# power_supply.net
KiCad netlist of a schematic drawn in EAGLE
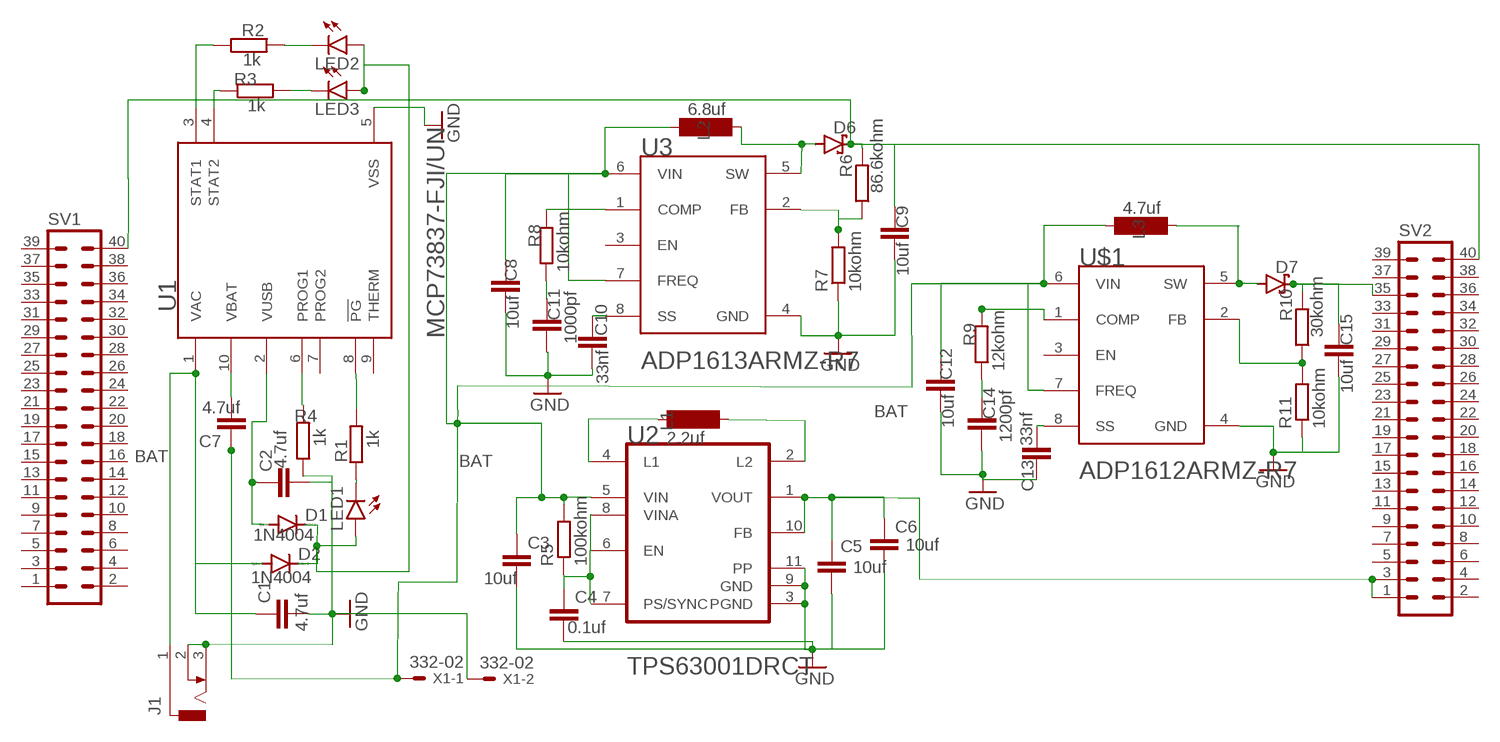
[diagram p0: schematic, sheet 1]

(export (version "E")
  (design (tool "Eeschema 10.0.6"))
  (components
    (comp (ref "C1")
      (value "4.7uf")
      (footprint "eagle-import:C025-024X044")
      (libsource (lib "eagle-import") (part "C-EU025-024X044"))
    )
    (comp (ref "C2")
      (value "4.7uf")
      (footprint "eagle-import:C025-024X044")
      (libsource (lib "eagle-import") (part "C-EU025-024X044"))
    )
    (comp (ref "C3")
      (value "10uf")
      (footprint "eagle-import:C0201")
      (libsource (lib "eagle-import") (part "C-EUC0201"))
    )
    (comp (ref "C4")
      (value "0.1uf")
      (footprint "eagle-import:C0201")
      (libsource (lib "eagle-import") (part "C-EUC0201"))
    )
    (comp (ref "C5")
      (value "10uf")
      (footprint "eagle-import:C0201")
      (libsource (lib "eagle-import") (part "C-EUC0201"))
    )
    (comp (ref "C6")
      (value "10uf")
      (footprint "eagle-import:C0201")
      (libsource (lib "eagle-import") (part "C-EUC0201"))
    )
    (comp (ref "C7")
      (value "4.7uf")
      (footprint "eagle-import:C025-024X044")
      (libsource (lib "eagle-import") (part "C-EU025-024X044"))
    )
    (comp (ref "C8")
      (value "10uf")
      (footprint "eagle-import:C0201")
      (libsource (lib "eagle-import") (part "C-EUC0201"))
    )
    (comp (ref "C9")
      (value "10uf")
      (footprint "eagle-import:C0201")
      (libsource (lib "eagle-import") (part "C-EUC0201"))
    )
    (comp (ref "C10")
      (value "33nf")
      (footprint "eagle-import:C0201")
      (libsource (lib "eagle-import") (part "C-EUC0201"))
    )
    (comp (ref "C11")
      (value "1000pf")
      (footprint "eagle-import:C0201")
      (libsource (lib "eagle-import") (part "C-EUC0201"))
    )
    (comp (ref "C12")
      (value "10uf")
      (footprint "eagle-import:C0201")
      (libsource (lib "eagle-import") (part "C-EUC0201"))
    )
    (comp (ref "C13")
      (value "33nf")
      (footprint "eagle-import:C0201")
      (libsource (lib "eagle-import") (part "C-EUC0201"))
    )
    (comp (ref "C14")
      (value "1200pf")
      (footprint "eagle-import:C0201")
      (libsource (lib "eagle-import") (part "C-EUC0201"))
    )
    (comp (ref "C15")
      (value "10uf")
      (footprint "eagle-import:C0201")
      (libsource (lib "eagle-import") (part "C-EUC0201"))
    )
    (comp (ref "D1")
      (value "1N4004")
      (footprint "eagle-import:DO41-10")
      (libsource (lib "eagle-import") (part "1N4004"))
    )
    (comp (ref "D2")
      (value "1N4004")
      (footprint "eagle-import:DO41-10")
      (libsource (lib "eagle-import") (part "1N4004"))
    )
    (comp (ref "D6")
      (value "P4KEXX")
      (footprint "eagle-import:DO41-10")
      (libsource (lib "eagle-import") (part "P4KEXX"))
    )
    (comp (ref "D7")
      (value "P4KEXX")
      (footprint "eagle-import:DO41-10")
      (libsource (lib "eagle-import") (part "P4KEXX"))
    )
    (comp (ref "J1")
      (value "DCJ0303")
      (footprint "eagle-import:DCJ0303")
      (libsource (lib "eagle-import") (part "DCJ0303"))
    )
    (comp (ref "L1")
      (value "2.2uf")
      (footprint "eagle-import:SD75")
      (libsource (lib "eagle-import") (part "SD75"))
    )
    (comp (ref "L2")
      (value "6.8uf")
      (footprint "eagle-import:SD75")
      (libsource (lib "eagle-import") (part "SD75"))
    )
    (comp (ref "L3")
      (value "4.7uf")
      (footprint "eagle-import:SD75")
      (libsource (lib "eagle-import") (part "SD75"))
    )
    (comp (ref "LED1")
      (value "LED")
      (footprint "eagle-import:SMARTLED-TTW")
      (libsource (lib "eagle-import") (part "LED"))
    )
    (comp (ref "LED2")
      (value "LED")
      (footprint "eagle-import:SMARTLED-TTW")
      (libsource (lib "eagle-import") (part "LED"))
    )
    (comp (ref "LED3")
      (value "LED")
      (footprint "eagle-import:SMARTLED-TTW")
      (libsource (lib "eagle-import") (part "LED"))
    )
    (comp (ref "R1")
      (value "1k")
      (footprint "eagle-import:R01005")
      (libsource (lib "eagle-import") (part "R-EU_01005"))
    )
    (comp (ref "R2")
      (value "1k")
      (footprint "eagle-import:R01005")
      (libsource (lib "eagle-import") (part "R-EU_01005"))
    )
    (comp (ref "R3")
      (value "1k")
      (footprint "eagle-import:R01005")
      (libsource (lib "eagle-import") (part "R-EU_01005"))
    )
    (comp (ref "R4")
      (value "1k")
      (footprint "eagle-import:R01005")
      (libsource (lib "eagle-import") (part "R-EU_01005"))
    )
    (comp (ref "R5")
      (value "100kohm")
      (footprint "eagle-import:R01005")
      (libsource (lib "eagle-import") (part "R-EU_01005"))
    )
    (comp (ref "R6")
      (value "86.6kohm")
      (footprint "eagle-import:R01005")
      (libsource (lib "eagle-import") (part "R-EU_01005"))
    )
    (comp (ref "R7")
      (value "10kohm")
      (footprint "eagle-import:R01005")
      (libsource (lib "eagle-import") (part "R-EU_01005"))
    )
    (comp (ref "R8")
      (value "10kohm")
      (footprint "eagle-import:R01005")
      (libsource (lib "eagle-import") (part "R-EU_01005"))
    )
    (comp (ref "R9")
      (value "12kohm")
      (footprint "eagle-import:R01005")
      (libsource (lib "eagle-import") (part "R-EU_01005"))
    )
    (comp (ref "R10")
      (value "30kohm")
      (footprint "eagle-import:R01005")
      (libsource (lib "eagle-import") (part "R-EU_01005"))
    )
    (comp (ref "R11")
      (value "10kohm")
      (footprint "eagle-import:R01005")
      (libsource (lib "eagle-import") (part "R-EU_01005"))
    )
    (comp (ref "SV1")
      (value "40P")
      (footprint "eagle-import:40P")
      (libsource (lib "eagle-import") (part "40P"))
    )
    (comp (ref "SV2")
      (value "40P")
      (footprint "eagle-import:40P")
      (libsource (lib "eagle-import") (part "40P"))
    )
    (comp (ref "U$1")
      (value "ADP1612")
      (footprint "eagle-import:ADP1612")
      (libsource (lib "eagle-import") (part "ADP1612"))
    )
    (comp (ref "U1")
      (value "MICROCHIP_MCP73837-FJI-UNMICROCHIP_MCP73837-FJI-UN_0_0")
      (footprint "eagle-import:MICROCHIP_MCP73837-FJI-UN_0")
      (fields
        (field (name "DIGIKEY_PART_NUMBER") "MCP73837-FJI/UN-ND")
        (field (name "MF") "Microchip")
        (field (name "MOUSER_PART_NUMBER") "579-MCP73837-FJI/UN")
      )
      (libsource (lib "eagle-import") (part "MICROCHIP_MCP73837-FJI-UNMICROCHIP_MCP73837-FJI-UN_0_0"))
    )
    (comp (ref "U2")
      (value "TEXAS_INSTRUMENTS_TPS63001DRCTTEXAS_INSTRUMENTS_TPS63001DRCT_0_0")
      (footprint "eagle-import:TEXAS_INSTRUMENTS_TPS63001DRCT_0")
      (fields (field (name "MF") "Texas Instruments") (field (name "MPN") "TPS63001DRCT"))
      (libsource (lib "eagle-import") (part "TEXAS_INSTRUMENTS_TPS63001DRCTTEXAS_INSTRUMENTS_TPS63001DRCT_0_0"))
    )
    (comp (ref "U3")
      (value "ANALOG_DEVICES_INC_ADP1613ARMZ-R7ANALOG_DEVICES_INC_ADP1613ARMZ-R7_0_0")
      (footprint "eagle-import:ANALOG_DEVICES_INC_ADP1613ARMZ-R7_0")
      (fields
        (field (name "DIGIKEY_PART_NUMBER") "ADP1613ARMZ-R7CT-ND")
        (field (name "MF") "Analog Devices Inc")
        (field (name "MOUSER_PART_NUMBER") "584-ADP1613ARMZ-R7")
      )
      (libsource (lib "eagle-import") (part "ANALOG_DEVICES_INC_ADP1613ARMZ-R7ANALOG_DEVICES_INC_ADP1613ARMZ-R7_0_0"))
    )
    (comp (ref "X1")
      (value "332-02")
      (footprint "eagle-import:332-02")
      (libsource (lib "eagle-import") (part "332-02"))
    )
  )
  (nets
    (net (code "1") (name "/BAT") (class "Default")
      (node (ref "C12") (pin "1") (pinfunction "1_1") (pintype "passive"))
      (node (ref "C3") (pin "1") (pinfunction "1_1") (pintype "passive"))
      (node (ref "C7") (pin "1") (pinfunction "1_1") (pintype "passive"))
      (node (ref "C8") (pin "1") (pinfunction "1_1") (pintype "passive"))
      (node (ref "L2") (pin "1") (pinfunction "1_1") (pintype "passive"))
      (node (ref "L3") (pin "1") (pinfunction "1_1") (pintype "passive"))
      (node (ref "R5") (pin "2") (pinfunction "2_2") (pintype "passive"))
      (node (ref "U$1") (pin "6") (pinfunction "VIN_6") (pintype "bidirectional"))
      (node (ref "U$1") (pin "7") (pinfunction "FREQ_7") (pintype "bidirectional"))
      (node (ref "U2") (pin "5") (pinfunction "VIN_5") (pintype "power_in"))
      (node (ref "U3") (pin "6") (pinfunction "VIN_6") (pintype "bidirectional"))
      (node (ref "U3") (pin "7") (pinfunction "FREQ_7") (pintype "bidirectional"))
      (node (ref "X1") (pin "1") (pinfunction "S_1") (pintype "passive"))
    )
    (net (code "2") (name "GND") (class "Default")
      (node (ref "C1") (pin "2") (pinfunction "2_2") (pintype "passive"))
      (node (ref "C10") (pin "2") (pinfunction "2_2") (pintype "passive"))
      (node (ref "C11") (pin "2") (pinfunction "2_2") (pintype "passive"))
      (node (ref "C12") (pin "2") (pinfunction "2_2") (pintype "passive"))
      (node (ref "C13") (pin "1") (pinfunction "1_1") (pintype "passive"))
      (node (ref "C14") (pin "2") (pinfunction "2_2") (pintype "passive"))
      (node (ref "C15") (pin "2") (pinfunction "2_2") (pintype "passive"))
      (node (ref "C2") (pin "2") (pinfunction "2_2") (pintype "passive"))
      (node (ref "C3") (pin "2") (pinfunction "2_2") (pintype "passive"))
      (node (ref "C4") (pin "2") (pinfunction "2_2") (pintype "passive"))
      (node (ref "C5") (pin "2") (pinfunction "2_2") (pintype "passive"))
      (node (ref "C6") (pin "2") (pinfunction "2_2") (pintype "passive"))
      (node (ref "C8") (pin "2") (pinfunction "2_2") (pintype "passive"))
      (node (ref "C9") (pin "2") (pinfunction "2_2") (pintype "passive"))
      (node (ref "J1") (pin "2") (pinfunction "2_2") (pintype "passive"))
      (node (ref "J1") (pin "3") (pinfunction "3_3") (pintype "passive"))
      (node (ref "R11") (pin "1") (pinfunction "1_1") (pintype "passive"))
      (node (ref "R4") (pin "1") (pinfunction "1_1") (pintype "passive"))
      (node (ref "R7") (pin "1") (pinfunction "1_1") (pintype "passive"))
      (node (ref "U$1") (pin "4") (pinfunction "GND_4") (pintype "power_in"))
      (node (ref "U1") (pin "5") (pinfunction "VSS_5") (pintype "bidirectional"))
      (node (ref "U2") (pin "11") (pinfunction "PP_11") (pintype "power_in"))
      (node (ref "U2") (pin "3") (pinfunction "PGND_3") (pintype "power_in"))
      (node (ref "U2") (pin "9") (pinfunction "GND_9") (pintype "power_in"))
      (node (ref "U3") (pin "4") (pinfunction "GND_4") (pintype "power_in"))
      (node (ref "X1") (pin "2") (pinfunction "S_2") (pintype "passive"))
    )
    (net (code "3") (name "Net-(C9-Pad1)") (class "Default")
      (node (ref "C9") (pin "1") (pinfunction "1_1") (pintype "passive"))
      (node (ref "D6") (pin "C") (pinfunction "C_C") (pintype "passive"))
      (node (ref "R6") (pin "2") (pinfunction "2_2") (pintype "passive"))
      (node (ref "SV1") (pin "40") (pinfunction "40_40") (pintype "passive"))
      (node (ref "SV2") (pin "40") (pinfunction "40_40") (pintype "passive"))
    )
    (net (code "4") (name "Net-(C11-Pad1)") (class "Default")
      (node (ref "C11") (pin "1") (pinfunction "1_1") (pintype "passive"))
      (node (ref "R8") (pin "1") (pinfunction "1_1") (pintype "passive"))
    )
    (net (code "5") (name "Net-(C14-Pad1)") (class "Default")
      (node (ref "C14") (pin "1") (pinfunction "1_1") (pintype "passive"))
      (node (ref "R9") (pin "1") (pinfunction "1_1") (pintype "passive"))
    )
    (net (code "6") (name "Net-(C15-Pad1)") (class "Default")
      (node (ref "C15") (pin "1") (pinfunction "1_1") (pintype "passive"))
      (node (ref "D7") (pin "C") (pinfunction "C_C") (pintype "passive"))
      (node (ref "R10") (pin "2") (pinfunction "2_2") (pintype "passive"))
      (node (ref "SV2") (pin "35") (pinfunction "35_35") (pintype "passive"))
    )
    (net (code "7") (name "Net-(LED1-A)") (class "Default")
      (node (ref "D1") (pin "C") (pinfunction "C_C") (pintype "passive"))
      (node (ref "D2") (pin "C") (pinfunction "C_C") (pintype "passive"))
      (node (ref "LED1") (pin "A@1") (pinfunction "A_A@1") (pintype "passive"))
      (node (ref "LED2") (pin "A@1") (pinfunction "A_A@1") (pintype "passive"))
      (node (ref "LED3") (pin "A@1") (pinfunction "A_A@1") (pintype "passive"))
    )
    (net (code "8") (name "Net-(LED1-C)") (class "Default")
      (node (ref "LED1") (pin "C@1") (pinfunction "C_C@1") (pintype "passive"))
      (node (ref "R1") (pin "1") (pinfunction "1_1") (pintype "passive"))
    )
    (net (code "9") (name "Net-(LED2-C)") (class "Default")
      (node (ref "LED2") (pin "C@1") (pinfunction "C_C@1") (pintype "passive"))
      (node (ref "R2") (pin "2") (pinfunction "2_2") (pintype "passive"))
    )
    (net (code "10") (name "Net-(LED3-C)") (class "Default")
      (node (ref "LED3") (pin "C@1") (pinfunction "C_C@1") (pintype "passive"))
      (node (ref "R3") (pin "2") (pinfunction "2_2") (pintype "passive"))
    )
    (net (code "11") (name "Net-(U$1-COMP)") (class "Default")
      (node (ref "R9") (pin "2") (pinfunction "2_2") (pintype "passive"))
      (node (ref "U$1") (pin "1") (pinfunction "COMP_1") (pintype "bidirectional"))
    )
    (net (code "12") (name "Net-(U$1-FB)") (class "Default")
      (node (ref "R10") (pin "1") (pinfunction "1_1") (pintype "passive"))
      (node (ref "R11") (pin "2") (pinfunction "2_2") (pintype "passive"))
      (node (ref "U$1") (pin "2") (pinfunction "FB_2") (pintype "bidirectional"))
    )
    (net (code "13") (name "Net-(U$1-SS)") (class "Default")
      (node (ref "C13") (pin "2") (pinfunction "2_2") (pintype "passive"))
      (node (ref "U$1") (pin "8") (pinfunction "SS_8") (pintype "bidirectional"))
    )
    (net (code "14") (name "Net-(U$1-SW)") (class "Default")
      (node (ref "D7") (pin "A") (pinfunction "A_A") (pintype "passive"))
      (node (ref "U$1") (pin "5") (pinfunction "SW_5") (pintype "bidirectional"))
    )
    (net (code "15") (name "Net-(U1-PROG1)") (class "Default")
      (node (ref "R4") (pin "2") (pinfunction "2_2") (pintype "passive"))
      (node (ref "U1") (pin "6") (pinfunction "PROG1_6") (pintype "bidirectional"))
    )
    (net (code "16") (name "Net-(U1-STAT1)") (class "Default")
      (node (ref "R2") (pin "1") (pinfunction "1_1") (pintype "passive"))
      (node (ref "U1") (pin "3") (pinfunction "STAT1_3") (pintype "bidirectional"))
    )
    (net (code "17") (name "Net-(U1-STAT2)") (class "Default")
      (node (ref "R3") (pin "1") (pinfunction "1_1") (pintype "passive"))
      (node (ref "U1") (pin "4") (pinfunction "STAT2_4") (pintype "bidirectional"))
    )
    (net (code "18") (name "Net-(U1-VAC)") (class "Default")
      (node (ref "C1") (pin "1") (pinfunction "1_1") (pintype "passive"))
      (node (ref "D2") (pin "A") (pinfunction "A_A") (pintype "passive"))
      (node (ref "J1") (pin "1") (pinfunction "1_1") (pintype "passive"))
      (node (ref "U1") (pin "1") (pinfunction "VAC_1") (pintype "bidirectional"))
    )
    (net (code "19") (name "Net-(U1-VBAT)") (class "Default")
      (node (ref "C7") (pin "2") (pinfunction "2_2") (pintype "passive"))
      (node (ref "U1") (pin "10") (pinfunction "VBAT_10") (pintype "bidirectional"))
    )
    (net (code "20") (name "Net-(U1-VUSB)") (class "Default")
      (node (ref "C2") (pin "1") (pinfunction "1_1") (pintype "passive"))
      (node (ref "D1") (pin "A") (pinfunction "A_A") (pintype "passive"))
      (node (ref "U1") (pin "2") (pinfunction "VUSB_2") (pintype "bidirectional"))
    )
    (net (code "21") (name "Net-(U1-~{PG})") (class "Default")
      (node (ref "R1") (pin "2") (pinfunction "2_2") (pintype "passive"))
      (node (ref "U1") (pin "8") (pinfunction "~{PG}_8") (pintype "bidirectional"))
    )
    (net (code "22") (name "Net-(U2-EN)") (class "Default")
      (node (ref "C4") (pin "1") (pinfunction "1_1") (pintype "passive"))
      (node (ref "R5") (pin "1") (pinfunction "1_1") (pintype "passive"))
      (node (ref "U2") (pin "6") (pinfunction "EN_6") (pintype "input"))
      (node (ref "U2") (pin "7") (pinfunction "PS/SYNC_7") (pintype "input"))
      (node (ref "U2") (pin "8") (pinfunction "VINA_8") (pintype "power_in"))
    )
    (net (code "23") (name "Net-(U2-FB)") (class "Default")
      (node (ref "C5") (pin "1") (pinfunction "1_1") (pintype "passive"))
      (node (ref "C6") (pin "1") (pinfunction "1_1") (pintype "passive"))
      (node (ref "SV2") (pin "1") (pinfunction "1_1") (pintype "passive"))
      (node (ref "SV2") (pin "3") (pinfunction "3_3") (pintype "passive"))
      (node (ref "U2") (pin "1") (pinfunction "VOUT_1") (pintype "power_in"))
      (node (ref "U2") (pin "10") (pinfunction "FB_10") (pintype "input"))
    )
    (net (code "24") (name "Net-(U2-L1)") (class "Default")
      (node (ref "L1") (pin "1") (pinfunction "1_1") (pintype "passive"))
      (node (ref "U2") (pin "4") (pinfunction "L1_4") (pintype "passive"))
    )
    (net (code "25") (name "Net-(U2-L2)") (class "Default")
      (node (ref "L1") (pin "2") (pinfunction "2_2") (pintype "passive"))
      (node (ref "U2") (pin "2") (pinfunction "L2_2") (pintype "passive"))
    )
    (net (code "26") (name "Net-(U3-COMP)") (class "Default")
      (node (ref "R8") (pin "2") (pinfunction "2_2") (pintype "passive"))
      (node (ref "U3") (pin "1") (pinfunction "COMP_1") (pintype "bidirectional"))
    )
    (net (code "27") (name "Net-(U3-FB)") (class "Default")
      (node (ref "R6") (pin "1") (pinfunction "1_1") (pintype "passive"))
      (node (ref "R7") (pin "2") (pinfunction "2_2") (pintype "passive"))
      (node (ref "U3") (pin "2") (pinfunction "FB_2") (pintype "bidirectional"))
    )
    (net (code "28") (name "Net-(U3-SS)") (class "Default")
      (node (ref "C10") (pin "1") (pinfunction "1_1") (pintype "passive"))
      (node (ref "U3") (pin "8") (pinfunction "SS_8") (pintype "bidirectional"))
    )
    (net (code "29") (name "Net-(U3-SW)") (class "Default")
      (node (ref "D6") (pin "A") (pinfunction "A_A") (pintype "passive"))
      (node (ref "L2") (pin "2") (pinfunction "2_2") (pintype "passive"))
      (node (ref "U3") (pin "5") (pinfunction "SW_5") (pintype "bidirectional"))
    )
    (net (code "30") (name "unconnected-(L3-Pad2)") (class "Default")
      (node (ref "L3") (pin "2") (pinfunction "2_2") (pintype "passive"))
    )
    (net (code "31") (name "unconnected-(SV1-Pad1)") (class "Default")
      (node (ref "SV1") (pin "1") (pinfunction "1_1") (pintype "passive"))
    )
    (net (code "32") (name "unconnected-(SV1-Pad2)") (class "Default")
      (node (ref "SV1") (pin "2") (pinfunction "2_2") (pintype "passive"))
    )
    (net (code "33") (name "unconnected-(SV1-Pad3)") (class "Default")
      (node (ref "SV1") (pin "3") (pinfunction "3_3") (pintype "passive"))
    )
    (net (code "34") (name "unconnected-(SV1-Pad4)") (class "Default")
      (node (ref "SV1") (pin "4") (pinfunction "4_4") (pintype "passive"))
    )
    (net (code "35") (name "unconnected-(SV1-Pad5)") (class "Default")
      (node (ref "SV1") (pin "5") (pinfunction "5_5") (pintype "passive"))
    )
    (net (code "36") (name "unconnected-(SV1-Pad6)") (class "Default")
      (node (ref "SV1") (pin "6") (pinfunction "6_6") (pintype "passive"))
    )
    (net (code "37") (name "unconnected-(SV1-Pad7)") (class "Default")
      (node (ref "SV1") (pin "7") (pinfunction "7_7") (pintype "passive"))
    )
    (net (code "38") (name "unconnected-(SV1-Pad8)") (class "Default")
      (node (ref "SV1") (pin "8") (pinfunction "8_8") (pintype "passive"))
    )
    (net (code "39") (name "unconnected-(SV1-Pad9)") (class "Default")
      (node (ref "SV1") (pin "9") (pinfunction "9_9") (pintype "passive"))
    )
    (net (code "40") (name "unconnected-(SV1-Pad10)") (class "Default")
      (node (ref "SV1") (pin "10") (pinfunction "10_10") (pintype "passive"))
    )
    (net (code "41") (name "unconnected-(SV1-Pad11)") (class "Default")
      (node (ref "SV1") (pin "11") (pinfunction "11_11") (pintype "passive"))
    )
    (net (code "42") (name "unconnected-(SV1-Pad12)") (class "Default")
      (node (ref "SV1") (pin "12") (pinfunction "12_12") (pintype "passive"))
    )
    (net (code "43") (name "unconnected-(SV1-Pad13)") (class "Default")
      (node (ref "SV1") (pin "13") (pinfunction "13_13") (pintype "passive"))
    )
    (net (code "44") (name "unconnected-(SV1-Pad14)") (class "Default")
      (node (ref "SV1") (pin "14") (pinfunction "14_14") (pintype "passive"))
    )
    (net (code "45") (name "unconnected-(SV1-Pad15)") (class "Default")
      (node (ref "SV1") (pin "15") (pinfunction "15_15") (pintype "passive"))
    )
    (net (code "46") (name "unconnected-(SV1-Pad16)") (class "Default")
      (node (ref "SV1") (pin "16") (pinfunction "16_16") (pintype "passive"))
    )
    (net (code "47") (name "unconnected-(SV1-Pad17)") (class "Default")
      (node (ref "SV1") (pin "17") (pinfunction "17_17") (pintype "passive"))
    )
    (net (code "48") (name "unconnected-(SV1-Pad18)") (class "Default")
      (node (ref "SV1") (pin "18") (pinfunction "18_18") (pintype "passive"))
    )
    (net (code "49") (name "unconnected-(SV1-Pad19)") (class "Default")
      (node (ref "SV1") (pin "19") (pinfunction "19_19") (pintype "passive"))
    )
    (net (code "50") (name "unconnected-(SV1-Pad20)") (class "Default")
      (node (ref "SV1") (pin "20") (pinfunction "20_20") (pintype "passive"))
    )
    (net (code "51") (name "unconnected-(SV1-Pad21)") (class "Default")
      (node (ref "SV1") (pin "21") (pinfunction "21_21") (pintype "passive"))
    )
    (net (code "52") (name "unconnected-(SV1-Pad22)") (class "Default")
      (node (ref "SV1") (pin "22") (pinfunction "22_22") (pintype "passive"))
    )
    (net (code "53") (name "unconnected-(SV1-Pad23)") (class "Default")
      (node (ref "SV1") (pin "23") (pinfunction "23_23") (pintype "passive"))
    )
    (net (code "54") (name "unconnected-(SV1-Pad24)") (class "Default")
      (node (ref "SV1") (pin "24") (pinfunction "24_24") (pintype "passive"))
    )
    (net (code "55") (name "unconnected-(SV1-Pad25)") (class "Default")
      (node (ref "SV1") (pin "25") (pinfunction "25_25") (pintype "passive"))
    )
    (net (code "56") (name "unconnected-(SV1-Pad26)") (class "Default")
      (node (ref "SV1") (pin "26") (pinfunction "26_26") (pintype "passive"))
    )
    (net (code "57") (name "unconnected-(SV1-Pad27)") (class "Default")
      (node (ref "SV1") (pin "27") (pinfunction "27_27") (pintype "passive"))
    )
    (net (code "58") (name "unconnected-(SV1-Pad28)") (class "Default")
      (node (ref "SV1") (pin "28") (pinfunction "28_28") (pintype "passive"))
    )
    (net (code "59") (name "unconnected-(SV1-Pad29)") (class "Default")
      (node (ref "SV1") (pin "29") (pinfunction "29_29") (pintype "passive"))
    )
    (net (code "60") (name "unconnected-(SV1-Pad30)") (class "Default")
      (node (ref "SV1") (pin "30") (pinfunction "30_30") (pintype "passive"))
    )
    (net (code "61") (name "unconnected-(SV1-Pad31)") (class "Default")
      (node (ref "SV1") (pin "31") (pinfunction "31_31") (pintype "passive"))
    )
    (net (code "62") (name "unconnected-(SV1-Pad32)") (class "Default")
      (node (ref "SV1") (pin "32") (pinfunction "32_32") (pintype "passive"))
    )
    (net (code "63") (name "unconnected-(SV1-Pad33)") (class "Default")
      (node (ref "SV1") (pin "33") (pinfunction "33_33") (pintype "passive"))
    )
    (net (code "64") (name "unconnected-(SV1-Pad34)") (class "Default")
      (node (ref "SV1") (pin "34") (pinfunction "34_34") (pintype "passive"))
    )
    (net (code "65") (name "unconnected-(SV1-Pad35)") (class "Default")
      (node (ref "SV1") (pin "35") (pinfunction "35_35") (pintype "passive"))
    )
    (net (code "66") (name "unconnected-(SV1-Pad36)") (class "Default")
      (node (ref "SV1") (pin "36") (pinfunction "36_36") (pintype "passive"))
    )
    (net (code "67") (name "unconnected-(SV1-Pad37)") (class "Default")
      (node (ref "SV1") (pin "37") (pinfunction "37_37") (pintype "passive"))
    )
    (net (code "68") (name "unconnected-(SV1-Pad38)") (class "Default")
      (node (ref "SV1") (pin "38") (pinfunction "38_38") (pintype "passive"))
    )
    (net (code "69") (name "unconnected-(SV1-Pad39)") (class "Default")
      (node (ref "SV1") (pin "39") (pinfunction "39_39") (pintype "passive"))
    )
    (net (code "70") (name "unconnected-(SV2-Pad2)") (class "Default")
      (node (ref "SV2") (pin "2") (pinfunction "2_2") (pintype "passive"))
    )
    (net (code "71") (name "unconnected-(SV2-Pad4)") (class "Default")
      (node (ref "SV2") (pin "4") (pinfunction "4_4") (pintype "passive"))
    )
    (net (code "72") (name "unconnected-(SV2-Pad5)") (class "Default")
      (node (ref "SV2") (pin "5") (pinfunction "5_5") (pintype "passive"))
    )
    (net (code "73") (name "unconnected-(SV2-Pad6)") (class "Default")
      (node (ref "SV2") (pin "6") (pinfunction "6_6") (pintype "passive"))
    )
    (net (code "74") (name "unconnected-(SV2-Pad7)") (class "Default")
      (node (ref "SV2") (pin "7") (pinfunction "7_7") (pintype "passive"))
    )
    (net (code "75") (name "unconnected-(SV2-Pad8)") (class "Default")
      (node (ref "SV2") (pin "8") (pinfunction "8_8") (pintype "passive"))
    )
    (net (code "76") (name "unconnected-(SV2-Pad9)") (class "Default")
      (node (ref "SV2") (pin "9") (pinfunction "9_9") (pintype "passive"))
    )
    (net (code "77") (name "unconnected-(SV2-Pad10)") (class "Default")
      (node (ref "SV2") (pin "10") (pinfunction "10_10") (pintype "passive"))
    )
    (net (code "78") (name "unconnected-(SV2-Pad11)") (class "Default")
      (node (ref "SV2") (pin "11") (pinfunction "11_11") (pintype "passive"))
    )
    (net (code "79") (name "unconnected-(SV2-Pad12)") (class "Default")
      (node (ref "SV2") (pin "12") (pinfunction "12_12") (pintype "passive"))
    )
    (net (code "80") (name "unconnected-(SV2-Pad13)") (class "Default")
      (node (ref "SV2") (pin "13") (pinfunction "13_13") (pintype "passive"))
    )
    (net (code "81") (name "unconnected-(SV2-Pad14)") (class "Default")
      (node (ref "SV2") (pin "14") (pinfunction "14_14") (pintype "passive"))
    )
    (net (code "82") (name "unconnected-(SV2-Pad15)") (class "Default")
      (node (ref "SV2") (pin "15") (pinfunction "15_15") (pintype "passive"))
    )
    (net (code "83") (name "unconnected-(SV2-Pad16)") (class "Default")
      (node (ref "SV2") (pin "16") (pinfunction "16_16") (pintype "passive"))
    )
    (net (code "84") (name "unconnected-(SV2-Pad17)") (class "Default")
      (node (ref "SV2") (pin "17") (pinfunction "17_17") (pintype "passive"))
    )
    (net (code "85") (name "unconnected-(SV2-Pad18)") (class "Default")
      (node (ref "SV2") (pin "18") (pinfunction "18_18") (pintype "passive"))
    )
    (net (code "86") (name "unconnected-(SV2-Pad19)") (class "Default")
      (node (ref "SV2") (pin "19") (pinfunction "19_19") (pintype "passive"))
    )
    (net (code "87") (name "unconnected-(SV2-Pad20)") (class "Default")
      (node (ref "SV2") (pin "20") (pinfunction "20_20") (pintype "passive"))
    )
    (net (code "88") (name "unconnected-(SV2-Pad21)") (class "Default")
      (node (ref "SV2") (pin "21") (pinfunction "21_21") (pintype "passive"))
    )
    (net (code "89") (name "unconnected-(SV2-Pad22)") (class "Default")
      (node (ref "SV2") (pin "22") (pinfunction "22_22") (pintype "passive"))
    )
    (net (code "90") (name "unconnected-(SV2-Pad23)") (class "Default")
      (node (ref "SV2") (pin "23") (pinfunction "23_23") (pintype "passive"))
    )
    (net (code "91") (name "unconnected-(SV2-Pad24)") (class "Default")
      (node (ref "SV2") (pin "24") (pinfunction "24_24") (pintype "passive"))
    )
    (net (code "92") (name "unconnected-(SV2-Pad25)") (class "Default")
      (node (ref "SV2") (pin "25") (pinfunction "25_25") (pintype "passive"))
    )
    (net (code "93") (name "unconnected-(SV2-Pad26)") (class "Default")
      (node (ref "SV2") (pin "26") (pinfunction "26_26") (pintype "passive"))
    )
    (net (code "94") (name "unconnected-(SV2-Pad27)") (class "Default")
      (node (ref "SV2") (pin "27") (pinfunction "27_27") (pintype "passive"))
    )
    (net (code "95") (name "unconnected-(SV2-Pad28)") (class "Default")
      (node (ref "SV2") (pin "28") (pinfunction "28_28") (pintype "passive"))
    )
    (net (code "96") (name "unconnected-(SV2-Pad29)") (class "Default")
      (node (ref "SV2") (pin "29") (pinfunction "29_29") (pintype "passive"))
    )
    (net (code "97") (name "unconnected-(SV2-Pad30)") (class "Default")
      (node (ref "SV2") (pin "30") (pinfunction "30_30") (pintype "passive"))
    )
    (net (code "98") (name "unconnected-(SV2-Pad31)") (class "Default")
      (node (ref "SV2") (pin "31") (pinfunction "31_31") (pintype "passive"))
    )
    (net (code "99") (name "unconnected-(SV2-Pad32)") (class "Default")
      (node (ref "SV2") (pin "32") (pinfunction "32_32") (pintype "passive"))
    )
    (net (code "100") (name "unconnected-(SV2-Pad33)") (class "Default")
      (node (ref "SV2") (pin "33") (pinfunction "33_33") (pintype "passive"))
    )
    (net (code "101") (name "unconnected-(SV2-Pad34)") (class "Default")
      (node (ref "SV2") (pin "34") (pinfunction "34_34") (pintype "passive"))
    )
    (net (code "102") (name "unconnected-(SV2-Pad36)") (class "Default")
      (node (ref "SV2") (pin "36") (pinfunction "36_36") (pintype "passive"))
    )
    (net (code "103") (name "unconnected-(SV2-Pad37)") (class "Default")
      (node (ref "SV2") (pin "37") (pinfunction "37_37") (pintype "passive"))
    )
    (net (code "104") (name "unconnected-(SV2-Pad38)") (class "Default")
      (node (ref "SV2") (pin "38") (pinfunction "38_38") (pintype "passive"))
    )
    (net (code "105") (name "unconnected-(SV2-Pad39)") (class "Default")
      (node (ref "SV2") (pin "39") (pinfunction "39_39") (pintype "passive"))
    )
    (net (code "106") (name "unconnected-(U$1-EN-Pad3)") (class "Default")
      (node (ref "U$1") (pin "3") (pinfunction "EN_3") (pintype "bidirectional"))
    )
    (net (code "107") (name "unconnected-(U1-PROG2-Pad7)") (class "Default")
      (node (ref "U1") (pin "7") (pinfunction "PROG2_7") (pintype "bidirectional"))
    )
    (net (code "108") (name "unconnected-(U1-THERM-Pad9)") (class "Default")
      (node (ref "U1") (pin "9") (pinfunction "THERM_9") (pintype "bidirectional"))
    )
    (net (code "109") (name "unconnected-(U3-EN-Pad3)") (class "Default")
      (node (ref "U3") (pin "3") (pinfunction "EN_3") (pintype "bidirectional"))
    )
  )
)
